# Mainboard.net
KiCad netlist of a schematic drawn in EAGLE
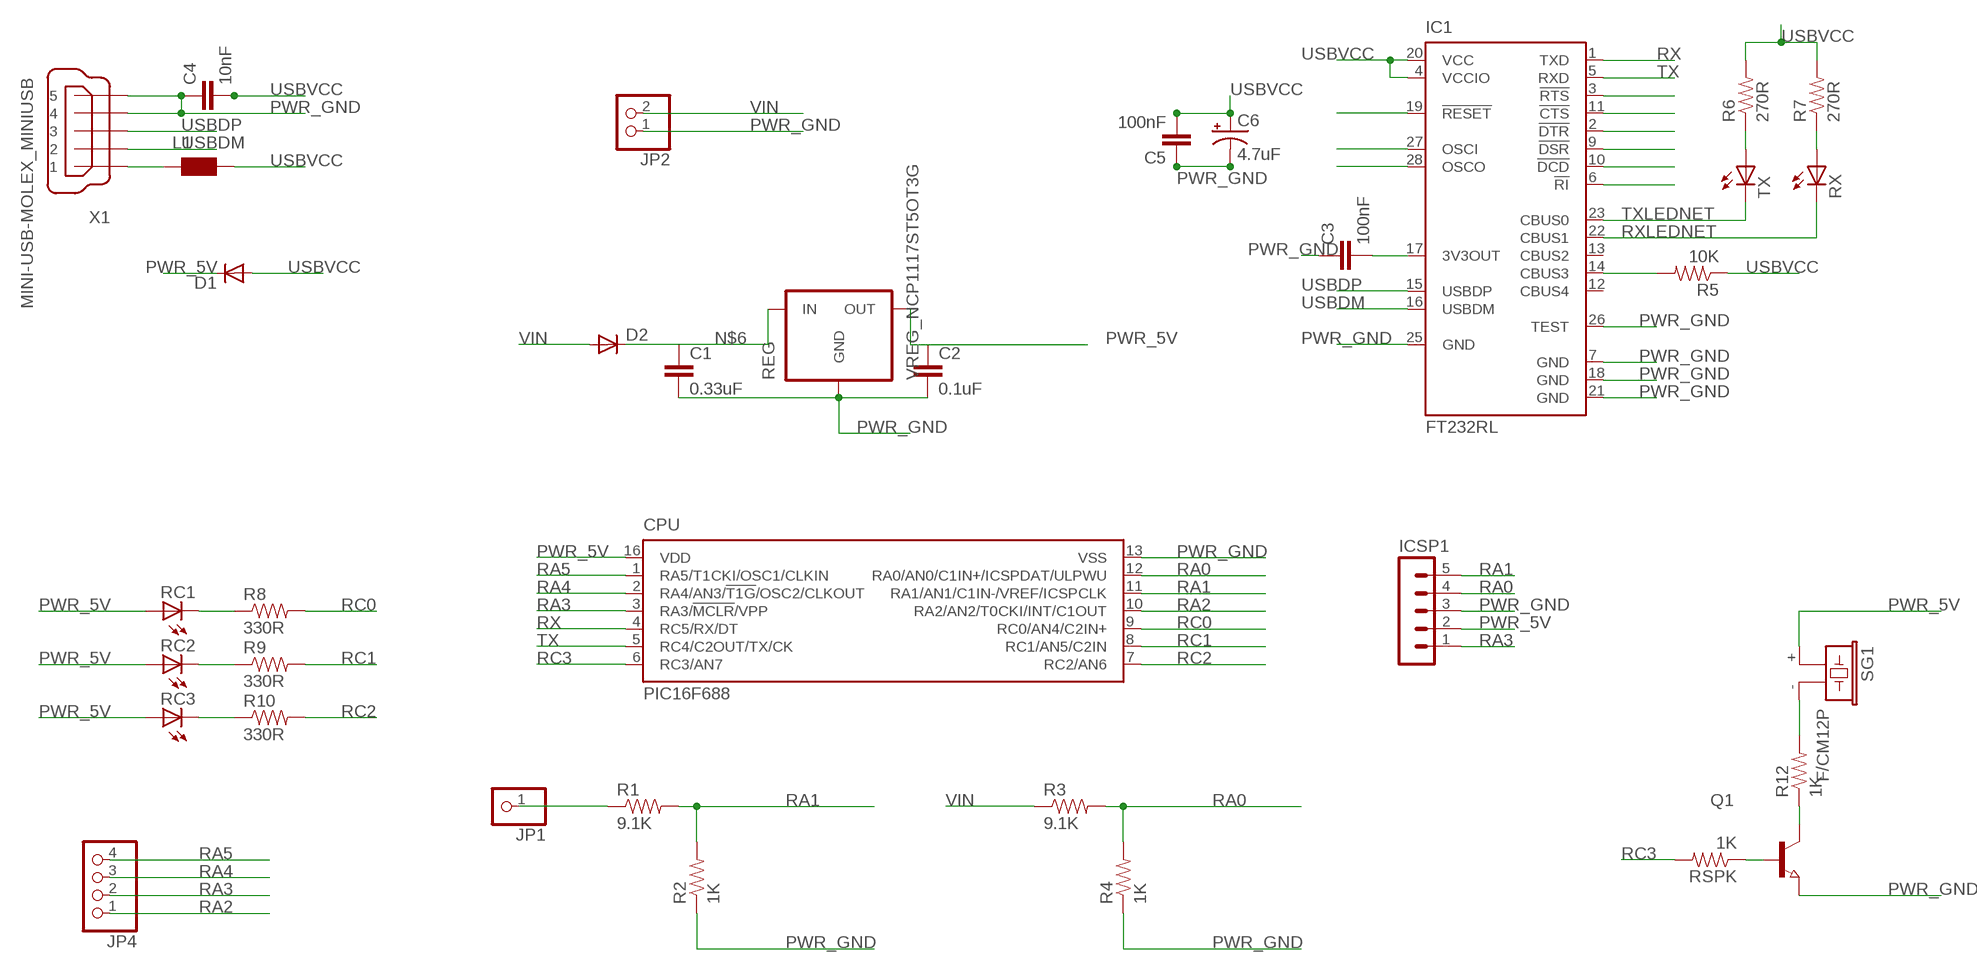
[diagram p0: schematic, sheet 1]

(export (version "E")
  (design (tool "Eeschema 10.0.6"))
  (components
    (comp (ref "C1")
      (value "0.33uF")
      (footprint "eagle-import:0805")
      (libsource (lib "eagle-import") (part "CAP0805"))
    )
    (comp (ref "C2")
      (value "0.1uF")
      (footprint "eagle-import:0805")
      (libsource (lib "eagle-import") (part "CAP0805"))
    )
    (comp (ref "C3")
      (value "100nF")
      (footprint "eagle-import:0805")
      (libsource (lib "eagle-import") (part "CAP0805"))
    )
    (comp (ref "C4")
      (value "10nF")
      (footprint "eagle-import:0805")
      (libsource (lib "eagle-import") (part "CAP0805"))
    )
    (comp (ref "C5")
      (value "100nF")
      (footprint "eagle-import:0805")
      (libsource (lib "eagle-import") (part "CAP0805"))
    )
    (comp (ref "C6")
      (value "4.7uF")
      (footprint "eagle-import:EIA3528")
      (libsource (lib "eagle-import") (part "CAP_POL3528"))
    )
    (comp (ref "CPU")
      (value "PIC16F688")
      (footprint "eagle-import:QFN16-4X4")
      (libsource (lib "eagle-import") (part "PIC16F688"))
    )
    (comp (ref "D1")
      (value "DIODESMA")
      (footprint "eagle-import:SMA-DIODE")
      (libsource (lib "eagle-import") (part "DIODESMA"))
    )
    (comp (ref "D2")
      (value "DIODESMA")
      (footprint "eagle-import:SMA-DIODE")
      (libsource (lib "eagle-import") (part "DIODESMA"))
    )
    (comp (ref "IC1")
      (value "FT232RL")
      (footprint "eagle-import:SSOP28")
      (libsource (lib "eagle-import") (part "FT232RL"))
    )
    (comp (ref "ICSP1")
      (value "MA05-1")
      (footprint "eagle-import:MA05-1")
      (libsource (lib "eagle-import") (part "MA05-1"))
    )
    (comp (ref "JP1")
      (value "PINHD-1X1")
      (footprint "eagle-import:1X01")
      (libsource (lib "eagle-import") (part "PINHD-1X1"))
    )
    (comp (ref "JP2")
      (value "PINHD-1X2")
      (footprint "eagle-import:1X02")
      (libsource (lib "eagle-import") (part "PINHD-1X2"))
    )
    (comp (ref "JP4")
      (value "PINHD-1X4")
      (footprint "eagle-import:1X04")
      (libsource (lib "eagle-import") (part "PINHD-1X4"))
    )
    (comp (ref "L1")
      (value "WE-CBF_0805")
      (footprint "eagle-import:0805")
      (libsource (lib "eagle-import") (part "WE-CBF_0805"))
    )
    (comp (ref "Q1")
      (value "NPN-TRANSISTOR_SOT23")
      (footprint "eagle-import:SOT23")
      (libsource (lib "eagle-import") (part "NPN-TRANSISTOR_SOT23"))
    )
    (comp (ref "R1")
      (value "9.1K")
      (footprint "eagle-import:0805")
      (libsource (lib "eagle-import") (part "RESISTOR"))
    )
    (comp (ref "R2")
      (value "1K")
      (footprint "eagle-import:0805")
      (libsource (lib "eagle-import") (part "RESISTOR"))
    )
    (comp (ref "R3")
      (value "9.1K")
      (footprint "eagle-import:0805")
      (libsource (lib "eagle-import") (part "RESISTOR"))
    )
    (comp (ref "R4")
      (value "1K")
      (footprint "eagle-import:0805")
      (libsource (lib "eagle-import") (part "RESISTOR"))
    )
    (comp (ref "R5")
      (value "10K")
      (footprint "eagle-import:0805")
      (libsource (lib "eagle-import") (part "RESISTOR"))
    )
    (comp (ref "R6")
      (value "270R")
      (footprint "eagle-import:0805")
      (libsource (lib "eagle-import") (part "RESISTOR"))
    )
    (comp (ref "R7")
      (value "270R")
      (footprint "eagle-import:0805")
      (libsource (lib "eagle-import") (part "RESISTOR"))
    )
    (comp (ref "R8")
      (value "330R")
      (footprint "eagle-import:0805")
      (libsource (lib "eagle-import") (part "RESISTOR"))
    )
    (comp (ref "R9")
      (value "330R")
      (footprint "eagle-import:0805")
      (libsource (lib "eagle-import") (part "RESISTOR"))
    )
    (comp (ref "R10")
      (value "330R")
      (footprint "eagle-import:0805")
      (libsource (lib "eagle-import") (part "RESISTOR"))
    )
    (comp (ref "R12")
      (value "1K")
      (footprint "eagle-import:0805")
      (libsource (lib "eagle-import") (part "RESISTOR"))
    )
    (comp (ref "RC1")
      (value "LED0603")
      (footprint "eagle-import:LED-0603")
      (libsource (lib "eagle-import") (part "LED0603"))
    )
    (comp (ref "RC2")
      (value "LED0603")
      (footprint "eagle-import:LED-0603")
      (libsource (lib "eagle-import") (part "LED0603"))
    )
    (comp (ref "RC3")
      (value "LED0603")
      (footprint "eagle-import:LED-0603")
      (libsource (lib "eagle-import") (part "LED0603"))
    )
    (comp (ref "REG")
      (value "VREG_NCP1117ST5OT3G")
      (footprint "eagle-import:SOT233")
      (libsource (lib "eagle-import") (part "VREG_NCP1117ST5OT3G"))
    )
    (comp (ref "RSPK")
      (value "1K")
      (footprint "eagle-import:0805")
      (libsource (lib "eagle-import") (part "RESISTOR"))
    )
    (comp (ref "RX")
      (value "LED0603")
      (footprint "eagle-import:LED-0603")
      (libsource (lib "eagle-import") (part "LED0603"))
    )
    (comp (ref "SG1")
      (value "F/CM12P")
      (footprint "eagle-import:F_CM12P")
      (libsource (lib "eagle-import") (part "F/CM12P"))
    )
    (comp (ref "TX")
      (value "LED0603")
      (footprint "eagle-import:LED-0603")
      (libsource (lib "eagle-import") (part "LED0603"))
    )
    (comp (ref "X1")
      (value "MINI-USB-MOLEX_MINIUSB")
      (footprint "eagle-import:32005-201")
      (libsource (lib "eagle-import") (part "MINI-USB-MOLEX_MINIUSB"))
    )
  )
  (nets
    (net (code "1") (name "/N$6") (class "Default")
      (node (ref "C1") (pin "1") (pinfunction "1_1") (pintype "passive"))
      (node (ref "D2") (pin "C") (pinfunction "C_C") (pintype "passive"))
      (node (ref "REG") (pin "3") (pinfunction "IN_3") (pintype "input"))
    )
    (net (code "2") (name "/PWR_5V") (class "Default")
      (node (ref "C2") (pin "1") (pinfunction "1_1") (pintype "passive"))
      (node (ref "CPU") (pin "16") (pinfunction "VDD_16") (pintype "power_in"))
      (node (ref "D1") (pin "C") (pinfunction "C_C") (pintype "passive"))
      (node (ref "ICSP1") (pin "2") (pinfunction "2_2") (pintype "passive"))
      (node (ref "RC1") (pin "A") (pinfunction "A_A") (pintype "passive"))
      (node (ref "RC2") (pin "A") (pinfunction "A_A") (pintype "passive"))
      (node (ref "RC3") (pin "A") (pinfunction "A_A") (pintype "passive"))
      (node (ref "REG") (pin "2") (pinfunction "OUT_2") (pintype "passive"))
      (node (ref "SG1") (pin "+") (pinfunction "1_+") (pintype "passive"))
    )
    (net (code "3") (name "/PWR_GND") (class "Default")
      (node (ref "C1") (pin "2") (pinfunction "2_2") (pintype "passive"))
      (node (ref "C2") (pin "2") (pinfunction "2_2") (pintype "passive"))
      (node (ref "C3") (pin "1") (pinfunction "1_1") (pintype "passive"))
      (node (ref "C4") (pin "1") (pinfunction "1_1") (pintype "passive"))
      (node (ref "C5") (pin "1") (pinfunction "1_1") (pintype "passive"))
      (node (ref "C6") (pin "C") (pinfunction "-_C") (pintype "passive"))
      (node (ref "CPU") (pin "13") (pinfunction "VSS_13") (pintype "power_in"))
      (node (ref "IC1") (pin "18") (pinfunction "GND_18") (pintype "power_in"))
      (node (ref "IC1") (pin "21") (pinfunction "GND_21") (pintype "power_in"))
      (node (ref "IC1") (pin "25") (pinfunction "GND_25") (pintype "power_in"))
      (node (ref "IC1") (pin "26") (pinfunction "TEST_26") (pintype "input"))
      (node (ref "IC1") (pin "7") (pinfunction "GND_7") (pintype "power_in"))
      (node (ref "ICSP1") (pin "3") (pinfunction "3_3") (pintype "passive"))
      (node (ref "JP2") (pin "1") (pinfunction "1_1") (pintype "passive"))
      (node (ref "Q1") (pin "2") (pinfunction "E_2") (pintype "passive"))
      (node (ref "R2") (pin "1") (pinfunction "1_1") (pintype "passive"))
      (node (ref "R4") (pin "1") (pinfunction "1_1") (pintype "passive"))
      (node (ref "REG") (pin "1") (pinfunction "GND_1") (pintype "input"))
      (node (ref "X1") (pin "4") (pinfunction "4_4") (pintype "passive"))
      (node (ref "X1") (pin "5") (pinfunction "5_5") (pintype "passive"))
    )
    (net (code "4") (name "/RA0") (class "Default")
      (node (ref "CPU") (pin "12") (pinfunction "RA0/AN0/C1IN+/ICSPDAT/ULPWU_12") (pintype "bidirectional"))
      (node (ref "ICSP1") (pin "4") (pinfunction "4_4") (pintype "passive"))
      (node (ref "R3") (pin "2") (pinfunction "2_2") (pintype "passive"))
      (node (ref "R4") (pin "2") (pinfunction "2_2") (pintype "passive"))
    )
    (net (code "5") (name "/RA1") (class "Default")
      (node (ref "CPU") (pin "11") (pinfunction "RA1/AN1/C1IN-/VREF/ICSPCLK_11") (pintype "bidirectional"))
      (node (ref "ICSP1") (pin "5") (pinfunction "5_5") (pintype "passive"))
      (node (ref "R1") (pin "2") (pinfunction "2_2") (pintype "passive"))
      (node (ref "R2") (pin "2") (pinfunction "2_2") (pintype "passive"))
    )
    (net (code "6") (name "/RA2") (class "Default")
      (node (ref "CPU") (pin "10") (pinfunction "RA2/AN2/T0CKI/INT/C1OUT_10") (pintype "bidirectional"))
      (node (ref "JP4") (pin "1") (pinfunction "1_1") (pintype "passive"))
    )
    (net (code "7") (name "/RA3") (class "Default")
      (node (ref "CPU") (pin "3") (pinfunction "RA3/~{MCLR}/VPP_3") (pintype "bidirectional"))
      (node (ref "ICSP1") (pin "1") (pinfunction "1_1") (pintype "passive"))
      (node (ref "JP4") (pin "2") (pinfunction "2_2") (pintype "passive"))
    )
    (net (code "8") (name "/RA4") (class "Default")
      (node (ref "CPU") (pin "2") (pinfunction "RA4/AN3/~{T1G}/OSC2/CLKOUT_2") (pintype "bidirectional"))
      (node (ref "JP4") (pin "3") (pinfunction "3_3") (pintype "passive"))
    )
    (net (code "9") (name "/RA5") (class "Default")
      (node (ref "CPU") (pin "1") (pinfunction "RA5/T1CKI/OSC1/CLKIN_1") (pintype "input"))
      (node (ref "JP4") (pin "4") (pinfunction "4_4") (pintype "passive"))
    )
    (net (code "10") (name "/RC0") (class "Default")
      (node (ref "CPU") (pin "9") (pinfunction "RC0/AN4/C2IN+_9") (pintype "bidirectional"))
      (node (ref "R8") (pin "2") (pinfunction "2_2") (pintype "passive"))
    )
    (net (code "11") (name "/RC1") (class "Default")
      (node (ref "CPU") (pin "8") (pinfunction "RC1/AN5/C2IN_8") (pintype "bidirectional"))
      (node (ref "R9") (pin "2") (pinfunction "2_2") (pintype "passive"))
    )
    (net (code "12") (name "/RC2") (class "Default")
      (node (ref "CPU") (pin "7") (pinfunction "RC2/AN6_7") (pintype "bidirectional"))
      (node (ref "R10") (pin "2") (pinfunction "2_2") (pintype "passive"))
    )
    (net (code "13") (name "/RC3") (class "Default")
      (node (ref "CPU") (pin "6") (pinfunction "RC3/AN7_6") (pintype "bidirectional"))
      (node (ref "RSPK") (pin "2") (pinfunction "2_2") (pintype "passive"))
    )
    (net (code "14") (name "/RX") (class "Default")
      (node (ref "CPU") (pin "4") (pinfunction "RC5/RX/DT_4") (pintype "bidirectional"))
      (node (ref "IC1") (pin "1") (pinfunction "TXD_1") (pintype "output"))
    )
    (net (code "15") (name "/RXLEDNET") (class "Default")
      (node (ref "IC1") (pin "22") (pinfunction "CBUS1_22") (pintype "bidirectional"))
      (node (ref "RX") (pin "C") (pinfunction "C_C") (pintype "passive"))
    )
    (net (code "16") (name "/TX") (class "Default")
      (node (ref "CPU") (pin "5") (pinfunction "RC4/C2OUT/TX/CK_5") (pintype "bidirectional"))
      (node (ref "IC1") (pin "5") (pinfunction "RXD_5") (pintype "input"))
    )
    (net (code "17") (name "/TXLEDNET") (class "Default")
      (node (ref "IC1") (pin "23") (pinfunction "CBUS0_23") (pintype "bidirectional"))
      (node (ref "TX") (pin "C") (pinfunction "C_C") (pintype "passive"))
    )
    (net (code "18") (name "/USBDM") (class "Default")
      (node (ref "IC1") (pin "16") (pinfunction "USBDM_16") (pintype "bidirectional"))
      (node (ref "X1") (pin "2") (pinfunction "2_2") (pintype "passive"))
    )
    (net (code "19") (name "/USBDP") (class "Default")
      (node (ref "IC1") (pin "15") (pinfunction "USBDP_15") (pintype "bidirectional"))
      (node (ref "X1") (pin "3") (pinfunction "3_3") (pintype "passive"))
    )
    (net (code "20") (name "/USBVCC") (class "Default")
      (node (ref "C4") (pin "2") (pinfunction "2_2") (pintype "passive"))
      (node (ref "C5") (pin "2") (pinfunction "2_2") (pintype "passive"))
      (node (ref "C6") (pin "A") (pinfunction "+_A") (pintype "passive"))
      (node (ref "D1") (pin "A") (pinfunction "A_A") (pintype "passive"))
      (node (ref "IC1") (pin "20") (pinfunction "VCC_20") (pintype "power_in"))
      (node (ref "IC1") (pin "4") (pinfunction "VCCIO_4") (pintype "power_in"))
      (node (ref "L1") (pin "2") (pinfunction "2_2") (pintype "passive"))
      (node (ref "R5") (pin "1") (pinfunction "1_1") (pintype "passive"))
      (node (ref "R6") (pin "2") (pinfunction "2_2") (pintype "passive"))
      (node (ref "R7") (pin "2") (pinfunction "2_2") (pintype "passive"))
    )
    (net (code "21") (name "/VIN") (class "Default")
      (node (ref "D2") (pin "A") (pinfunction "A_A") (pintype "passive"))
      (node (ref "JP2") (pin "2") (pinfunction "2_2") (pintype "passive"))
      (node (ref "R3") (pin "1") (pinfunction "1_1") (pintype "passive"))
    )
    (net (code "22") (name "Net-(IC1-3V3OUT)") (class "Default")
      (node (ref "C3") (pin "2") (pinfunction "2_2") (pintype "passive"))
      (node (ref "IC1") (pin "17") (pinfunction "3V3OUT_17") (pintype "output"))
    )
    (net (code "23") (name "Net-(IC1-CBUS3)") (class "Default")
      (node (ref "IC1") (pin "14") (pinfunction "CBUS3_14") (pintype "bidirectional"))
      (node (ref "R5") (pin "2") (pinfunction "2_2") (pintype "passive"))
    )
    (net (code "24") (name "Net-(JP1-Pad1)") (class "Default")
      (node (ref "JP1") (pin "1") (pinfunction "1_1") (pintype "passive"))
      (node (ref "R1") (pin "1") (pinfunction "1_1") (pintype "passive"))
    )
    (net (code "25") (name "Net-(L1-Pad1)") (class "Default")
      (node (ref "L1") (pin "1") (pinfunction "1_1") (pintype "passive"))
      (node (ref "X1") (pin "1") (pinfunction "1_1") (pintype "passive"))
    )
    (net (code "26") (name "Net-(Q1-B)") (class "Default")
      (node (ref "Q1") (pin "1") (pinfunction "B_1") (pintype "passive"))
      (node (ref "RSPK") (pin "1") (pinfunction "1_1") (pintype "passive"))
    )
    (net (code "27") (name "Net-(Q1-C)") (class "Default")
      (node (ref "Q1") (pin "3") (pinfunction "C_3") (pintype "passive"))
      (node (ref "R12") (pin "1") (pinfunction "1_1") (pintype "passive"))
    )
    (net (code "28") (name "Net-(R6-Pad1)") (class "Default")
      (node (ref "R6") (pin "1") (pinfunction "1_1") (pintype "passive"))
      (node (ref "TX") (pin "A") (pinfunction "A_A") (pintype "passive"))
    )
    (net (code "29") (name "Net-(R7-Pad1)") (class "Default")
      (node (ref "R7") (pin "1") (pinfunction "1_1") (pintype "passive"))
      (node (ref "RX") (pin "A") (pinfunction "A_A") (pintype "passive"))
    )
    (net (code "30") (name "Net-(R8-Pad1)") (class "Default")
      (node (ref "R8") (pin "1") (pinfunction "1_1") (pintype "passive"))
      (node (ref "RC1") (pin "C") (pinfunction "C_C") (pintype "passive"))
    )
    (net (code "31") (name "Net-(R9-Pad1)") (class "Default")
      (node (ref "R9") (pin "1") (pinfunction "1_1") (pintype "passive"))
      (node (ref "RC2") (pin "C") (pinfunction "C_C") (pintype "passive"))
    )
    (net (code "32") (name "Net-(R10-Pad1)") (class "Default")
      (node (ref "R10") (pin "1") (pinfunction "1_1") (pintype "passive"))
      (node (ref "RC3") (pin "C") (pinfunction "C_C") (pintype "passive"))
    )
    (net (code "33") (name "Net-(SG1-2)") (class "Default")
      (node (ref "R12") (pin "2") (pinfunction "2_2") (pintype "passive"))
      (node (ref "SG1") (pin "-") (pinfunction "2_-") (pintype "passive"))
    )
    (net (code "34") (name "unconnected-(IC1-CBUS2-Pad13)") (class "Default")
      (node (ref "IC1") (pin "13") (pinfunction "CBUS2_13") (pintype "bidirectional"))
    )
    (net (code "35") (name "unconnected-(IC1-CBUS4-Pad12)") (class "Default")
      (node (ref "IC1") (pin "12") (pinfunction "CBUS4_12") (pintype "bidirectional"))
    )
    (net (code "36") (name "unconnected-(IC1-OSCI-Pad27)") (class "Default")
      (node (ref "IC1") (pin "27") (pinfunction "OSCI_27") (pintype "input"))
    )
    (net (code "37") (name "unconnected-(IC1-OSCO-Pad28)") (class "Default")
      (node (ref "IC1") (pin "28") (pinfunction "OSCO_28") (pintype "output"))
    )
    (net (code "38") (name "unconnected-(IC1-~{CTS}-Pad11)") (class "Default")
      (node (ref "IC1") (pin "11") (pinfunction "~{CTS}_11") (pintype "input"))
    )
    (net (code "39") (name "unconnected-(IC1-~{DCD}-Pad10)") (class "Default")
      (node (ref "IC1") (pin "10") (pinfunction "~{DCD}_10") (pintype "input"))
    )
    (net (code "40") (name "unconnected-(IC1-~{DSR}-Pad9)") (class "Default")
      (node (ref "IC1") (pin "9") (pinfunction "~{DSR}_9") (pintype "input"))
    )
    (net (code "41") (name "unconnected-(IC1-~{DTR}-Pad2)") (class "Default")
      (node (ref "IC1") (pin "2") (pinfunction "~{DTR}_2") (pintype "output"))
    )
    (net (code "42") (name "unconnected-(IC1-~{RESET}-Pad19)") (class "Default")
      (node (ref "IC1") (pin "19") (pinfunction "~{RESET}_19") (pintype "input"))
    )
    (net (code "43") (name "unconnected-(IC1-~{RI}-Pad6)") (class "Default")
      (node (ref "IC1") (pin "6") (pinfunction "~{RI}_6") (pintype "input"))
    )
    (net (code "44") (name "unconnected-(IC1-~{RTS}-Pad3)") (class "Default")
      (node (ref "IC1") (pin "3") (pinfunction "~{RTS}_3") (pintype "output"))
    )
  )
)
